# test2.net
KiCad netlist of a schematic drawn in EAGLE
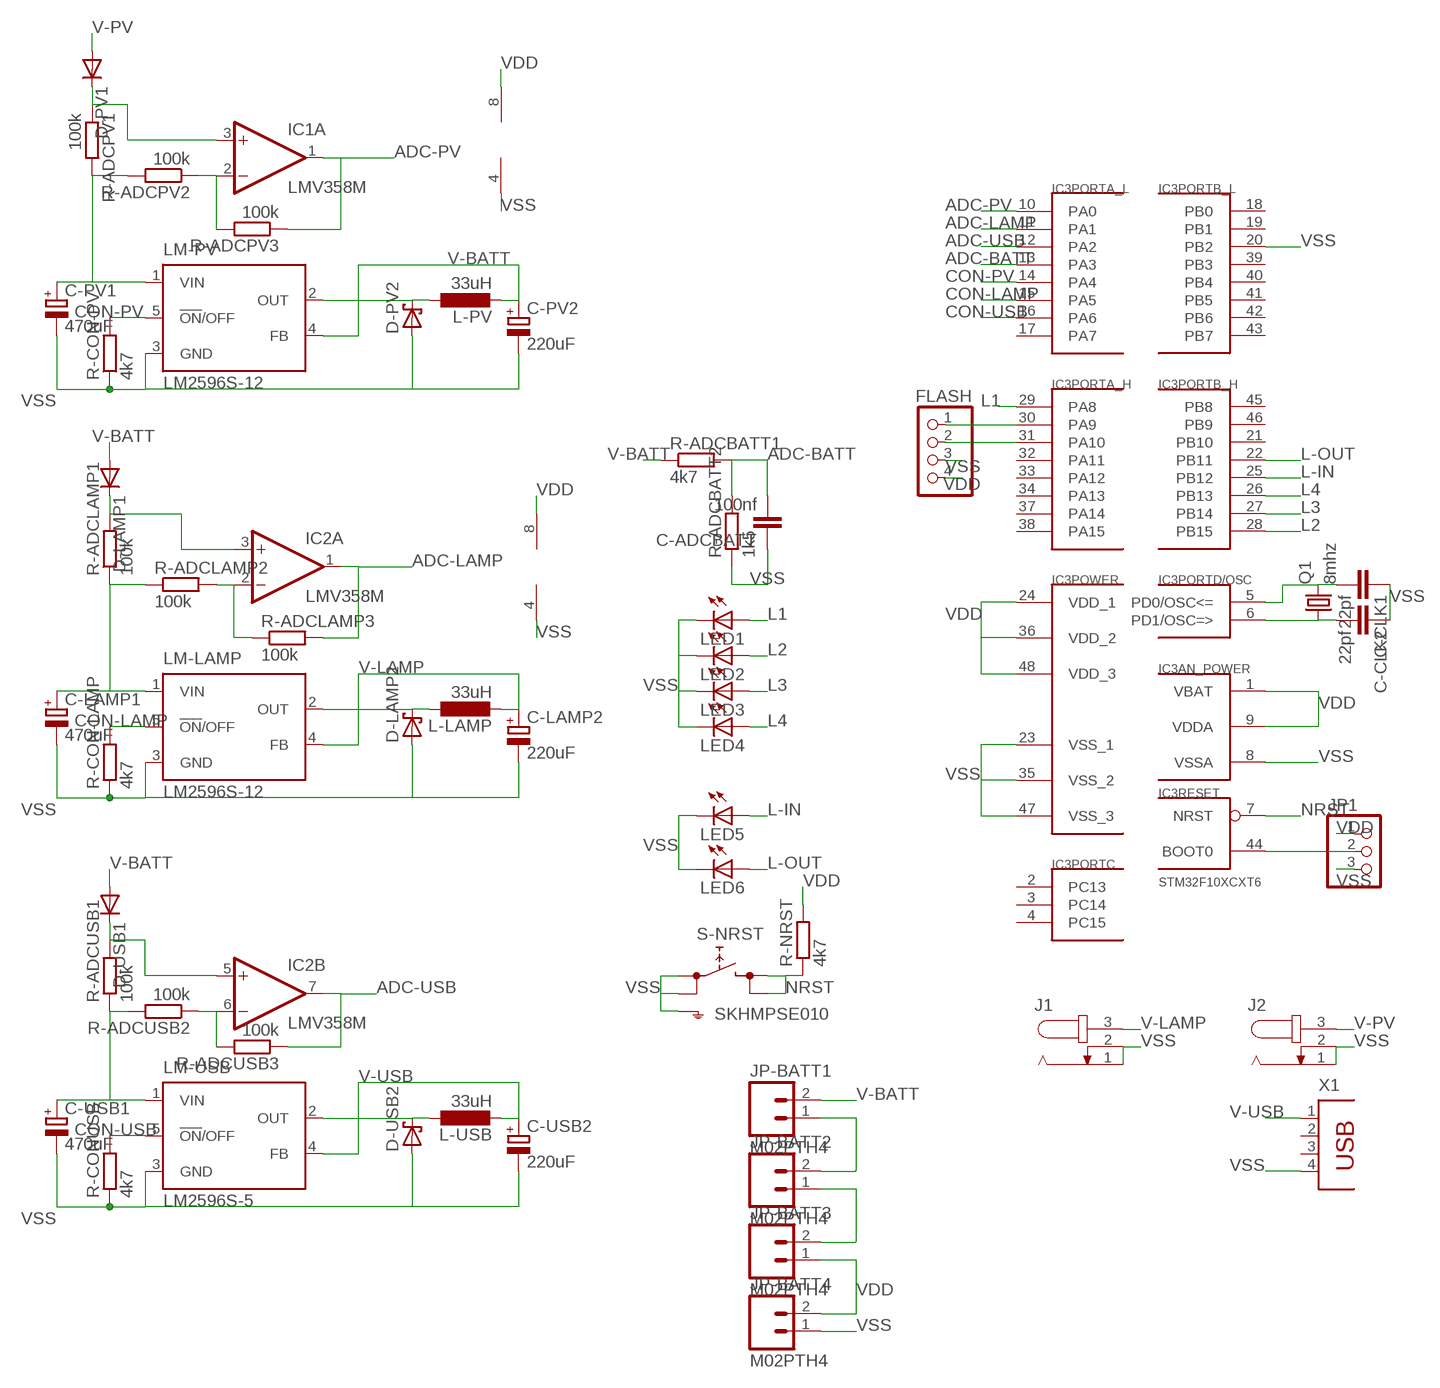
[diagram p0: schematic, sheet 1]

(export (version "E")
  (design (tool "Eeschema 10.0.6"))
  (components
    (comp (ref "C-ADCBATT")
      (value "100nf")
      (footprint "eagle-import:C0805")
      (libsource (lib "eagle-import") (part "C-EUC0805"))
    )
    (comp (ref "C-CLK1")
      (value "22pf")
      (footprint "eagle-import:C0805")
      (libsource (lib "eagle-import") (part "C-EUC0805"))
    )
    (comp (ref "C-CLK2")
      (value "22pf")
      (footprint "eagle-import:C0805")
      (libsource (lib "eagle-import") (part "C-EUC0805"))
    )
    (comp (ref "C-LAMP1")
      (value "470uF")
      (footprint "eagle-import:E2,5-5")
      (libsource (lib "eagle-import") (part "CPOL-EUE2.5-5"))
    )
    (comp (ref "C-LAMP2")
      (value "220uF")
      (footprint "eagle-import:E2,5-5")
      (libsource (lib "eagle-import") (part "CPOL-EUE2.5-5"))
    )
    (comp (ref "C-PV1")
      (value "470uF")
      (footprint "eagle-import:E2,5-5")
      (libsource (lib "eagle-import") (part "CPOL-EUE2.5-5"))
    )
    (comp (ref "C-PV2")
      (value "220uF")
      (footprint "eagle-import:E2,5-5")
      (libsource (lib "eagle-import") (part "CPOL-EUE2.5-5"))
    )
    (comp (ref "C-USB1")
      (value "470uF")
      (footprint "eagle-import:E2,5-5")
      (libsource (lib "eagle-import") (part "CPOL-EUE2.5-5"))
    )
    (comp (ref "C-USB2")
      (value "220uF")
      (footprint "eagle-import:E2,5-5")
      (libsource (lib "eagle-import") (part "CPOL-EUE2.5-5"))
    )
    (comp (ref "D-LAMP1")
      (value "DIODE-DO-214AC")
      (footprint "eagle-import:DO-214AC")
      (libsource (lib "eagle-import") (part "DIODE-DO-214AC"))
    )
    (comp (ref "D-LAMP2")
      (value "SCHOTTKY-DIODE")
      (footprint "eagle-import:DIODE_SMB")
      (libsource (lib "eagle-import") (part "SCHOTTKY-DIODE"))
    )
    (comp (ref "D-PV1")
      (value "DIODE-DO-214AC")
      (footprint "eagle-import:DO-214AC")
      (libsource (lib "eagle-import") (part "DIODE-DO-214AC"))
    )
    (comp (ref "D-PV2")
      (value "SCHOTTKY-DIODE")
      (footprint "eagle-import:DIODE_SMB")
      (libsource (lib "eagle-import") (part "SCHOTTKY-DIODE"))
    )
    (comp (ref "D-USB1")
      (value "DIODE-DO-214AC")
      (footprint "eagle-import:DO-214AC")
      (libsource (lib "eagle-import") (part "DIODE-DO-214AC"))
    )
    (comp (ref "D-USB2")
      (value "SCHOTTKY-DIODE")
      (footprint "eagle-import:DIODE_SMB")
      (libsource (lib "eagle-import") (part "SCHOTTKY-DIODE"))
    )
    (comp (ref "FLASH")
      (value "PINHD-1X4")
      (footprint "eagle-import:1X04")
      (libsource (lib "eagle-import") (part "PINHD-1X4"))
    )
    (comp (ref "IC1")
      (value "LMV358M")
      (footprint "eagle-import:SO08")
      (libsource (lib "eagle-import") (part "LMV358?M"))
    )
    (comp (ref "IC2")
      (value "LMV358M")
      (footprint "eagle-import:SO08")
      (libsource (lib "eagle-import") (part "LMV358?M"))
    )
    (comp (ref "IC3")
      (value "STM32F10XCXT6")
      (footprint "eagle-import:TQFP48")
      (libsource (lib "eagle-import") (part "STM32F10XCXT6"))
    )
    (comp (ref "J1")
      (value "JACK-PLUG0")
      (footprint "eagle-import:SPC4077")
      (libsource (lib "eagle-import") (part "JACK-PLUG0"))
    )
    (comp (ref "J2")
      (value "JACK-PLUG0")
      (footprint "eagle-import:SPC4077")
      (libsource (lib "eagle-import") (part "JACK-PLUG0"))
    )
    (comp (ref "JP-BATT1")
      (value "M02PTH4")
      (footprint "eagle-import:1X02_XTRA_BIG")
      (libsource (lib "eagle-import") (part "M02PTH4"))
    )
    (comp (ref "JP-BATT2")
      (value "M02PTH4")
      (footprint "eagle-import:1X02_XTRA_BIG")
      (libsource (lib "eagle-import") (part "M02PTH4"))
    )
    (comp (ref "JP-BATT3")
      (value "M02PTH4")
      (footprint "eagle-import:1X02_XTRA_BIG")
      (libsource (lib "eagle-import") (part "M02PTH4"))
    )
    (comp (ref "JP-BATT4")
      (value "M02PTH4")
      (footprint "eagle-import:1X02_XTRA_BIG")
      (libsource (lib "eagle-import") (part "M02PTH4"))
    )
    (comp (ref "JP1")
      (value "PINHD-1X3")
      (footprint "eagle-import:1X03")
      (libsource (lib "eagle-import") (part "PINHD-1X3"))
    )
    (comp (ref "L-LAMP")
      (value "33uH")
      (footprint "eagle-import:POWER-CHOKE_WE-TPC")
      (libsource (lib "eagle-import") (part "L-EUWE-TPC"))
    )
    (comp (ref "L-PV")
      (value "33uH")
      (footprint "eagle-import:POWER-CHOKE_WE-TPC")
      (libsource (lib "eagle-import") (part "L-EUWE-TPC"))
    )
    (comp (ref "L-USB")
      (value "33uH")
      (footprint "eagle-import:POWER-CHOKE_WE-TPC")
      (libsource (lib "eagle-import") (part "L-EUWE-TPC"))
    )
    (comp (ref "LED1")
      (value "LEDCHIP-LED0805")
      (footprint "eagle-import:CHIP-LED0805")
      (libsource (lib "eagle-import") (part "LEDCHIP-LED0805"))
    )
    (comp (ref "LED2")
      (value "LEDCHIP-LED0805")
      (footprint "eagle-import:CHIP-LED0805")
      (libsource (lib "eagle-import") (part "LEDCHIP-LED0805"))
    )
    (comp (ref "LED3")
      (value "LEDCHIP-LED0805")
      (footprint "eagle-import:CHIP-LED0805")
      (libsource (lib "eagle-import") (part "LEDCHIP-LED0805"))
    )
    (comp (ref "LED4")
      (value "LEDCHIP-LED0805")
      (footprint "eagle-import:CHIP-LED0805")
      (libsource (lib "eagle-import") (part "LEDCHIP-LED0805"))
    )
    (comp (ref "LED5")
      (value "LEDCHIP-LED0805")
      (footprint "eagle-import:CHIP-LED0805")
      (libsource (lib "eagle-import") (part "LEDCHIP-LED0805"))
    )
    (comp (ref "LED6")
      (value "LEDCHIP-LED0805")
      (footprint "eagle-import:CHIP-LED0805")
      (libsource (lib "eagle-import") (part "LEDCHIP-LED0805"))
    )
    (comp (ref "LM-LAMP")
      (value "LM2596S-12")
      (footprint "eagle-import:TO263-5")
      (fields (field (name "MF") "NATIONAL SEMICONDUCTOR") (field (name "MPN") "LM2596S-ADJ/NOPB"))
      (libsource (lib "eagle-import") (part "LM2596S"))
    )
    (comp (ref "LM-PV")
      (value "LM2596S-12")
      (footprint "eagle-import:TO263-5")
      (fields (field (name "MF") "NATIONAL SEMICONDUCTOR") (field (name "MPN") "LM2596S-ADJ/NOPB"))
      (libsource (lib "eagle-import") (part "LM2596S"))
    )
    (comp (ref "LM-USB")
      (value "LM2596S-5")
      (footprint "eagle-import:TO263-5")
      (fields (field (name "MF") "NATIONAL SEMICONDUCTOR") (field (name "MPN") "LM2596S-ADJ/NOPB"))
      (libsource (lib "eagle-import") (part "LM2596S"))
    )
    (comp (ref "Q1")
      (value "8mhz")
      (footprint "eagle-import:HC49_S")
      (libsource (lib "eagle-import") (part "CRYSTALHC49S"))
    )
    (comp (ref "R-ADCBATT1")
      (value "4k7")
      (footprint "eagle-import:R0805")
      (libsource (lib "eagle-import") (part "R-EU_R0805"))
    )
    (comp (ref "R-ADCBATT2")
      (value "1k5")
      (footprint "eagle-import:R0805")
      (libsource (lib "eagle-import") (part "R-EU_R0805"))
    )
    (comp (ref "R-ADCLAMP1")
      (value "100k")
      (footprint "eagle-import:R0805")
      (libsource (lib "eagle-import") (part "R-EU_R0805"))
    )
    (comp (ref "R-ADCLAMP2")
      (value "100k")
      (footprint "eagle-import:R0805")
      (libsource (lib "eagle-import") (part "R-EU_R0805"))
    )
    (comp (ref "R-ADCLAMP3")
      (value "100k")
      (footprint "eagle-import:R0805")
      (libsource (lib "eagle-import") (part "R-EU_R0805"))
    )
    (comp (ref "R-ADCPV1")
      (value "100k")
      (footprint "eagle-import:R0805")
      (libsource (lib "eagle-import") (part "R-EU_R0805"))
    )
    (comp (ref "R-ADCPV2")
      (value "100k")
      (footprint "eagle-import:R0805")
      (libsource (lib "eagle-import") (part "R-EU_R0805"))
    )
    (comp (ref "R-ADCPV3")
      (value "100k")
      (footprint "eagle-import:R0805")
      (libsource (lib "eagle-import") (part "R-EU_R0805"))
    )
    (comp (ref "R-ADCUSB1")
      (value "100k")
      (footprint "eagle-import:R0805")
      (libsource (lib "eagle-import") (part "R-EU_R0805"))
    )
    (comp (ref "R-ADCUSB2")
      (value "100k")
      (footprint "eagle-import:R0805")
      (libsource (lib "eagle-import") (part "R-EU_R0805"))
    )
    (comp (ref "R-ADCUSB3")
      (value "100k")
      (footprint "eagle-import:R0805")
      (libsource (lib "eagle-import") (part "R-EU_R0805"))
    )
    (comp (ref "R-CON-LAMP")
      (value "4k7")
      (footprint "eagle-import:R0805")
      (libsource (lib "eagle-import") (part "R-EU_R0805"))
    )
    (comp (ref "R-CON-PV")
      (value "4k7")
      (footprint "eagle-import:R0805")
      (libsource (lib "eagle-import") (part "R-EU_R0805"))
    )
    (comp (ref "R-CONUSB")
      (value "4k7")
      (footprint "eagle-import:R0805")
      (libsource (lib "eagle-import") (part "R-EU_R0805"))
    )
    (comp (ref "R-NRST")
      (value "4k7")
      (footprint "eagle-import:R0805")
      (libsource (lib "eagle-import") (part "R-EU_R0805"))
    )
    (comp (ref "S-NRST")
      (value "SKHMPSE010")
      (footprint "eagle-import:SKHMPXE010")
      (libsource (lib "eagle-import") (part "SKHMPE010S"))
    )
    (comp (ref "X1")
      (value "PN87520")
      (footprint "eagle-import:PN87520")
      (libsource (lib "eagle-import") (part "PN87520"))
    )
  )
  (nets
    (net (code "1") (name "/ADC-BATT") (class "Default")
      (node (ref "C-ADCBATT") (pin "2") (pinfunction "2_2") (pintype "passive"))
      (node (ref "IC3") (pin "13") (pinfunction "PA3_13") (pintype "bidirectional"))
      (node (ref "R-ADCBATT1") (pin "2") (pinfunction "2_2") (pintype "passive"))
      (node (ref "R-ADCBATT2") (pin "2") (pinfunction "2_2") (pintype "passive"))
    )
    (net (code "2") (name "/ADC-LAMP") (class "Default")
      (node (ref "IC2") (pin "1") (pinfunction "OUT_1") (pintype "output"))
      (node (ref "IC3") (pin "11") (pinfunction "PA1_11") (pintype "bidirectional"))
      (node (ref "R-ADCLAMP3") (pin "2") (pinfunction "2_2") (pintype "passive"))
    )
    (net (code "3") (name "/ADC-PV") (class "Default")
      (node (ref "IC1") (pin "1") (pinfunction "OUT_1") (pintype "output"))
      (node (ref "IC3") (pin "10") (pinfunction "PA0_10") (pintype "bidirectional"))
      (node (ref "R-ADCPV3") (pin "1") (pinfunction "1_1") (pintype "passive"))
    )
    (net (code "4") (name "/ADC-USB") (class "Default")
      (node (ref "IC2") (pin "7") (pinfunction "OUT_7") (pintype "output"))
      (node (ref "IC3") (pin "12") (pinfunction "PA2_12") (pintype "bidirectional"))
      (node (ref "R-ADCUSB3") (pin "1") (pinfunction "1_1") (pintype "passive"))
    )
    (net (code "5") (name "/CON-LAMP") (class "Default")
      (node (ref "IC3") (pin "15") (pinfunction "PA5_15") (pintype "bidirectional"))
      (node (ref "LM-LAMP") (pin "5") (pinfunction "~{ON}/OFF_5") (pintype "input"))
      (node (ref "R-CON-LAMP") (pin "2") (pinfunction "2_2") (pintype "passive"))
    )
    (net (code "6") (name "/CON-PV") (class "Default")
      (node (ref "IC3") (pin "14") (pinfunction "PA4_14") (pintype "bidirectional"))
      (node (ref "LM-PV") (pin "5") (pinfunction "~{ON}/OFF_5") (pintype "input"))
      (node (ref "R-CON-PV") (pin "2") (pinfunction "2_2") (pintype "passive"))
    )
    (net (code "7") (name "/CON-USB") (class "Default")
      (node (ref "IC3") (pin "16") (pinfunction "PA6_16") (pintype "bidirectional"))
      (node (ref "LM-USB") (pin "5") (pinfunction "~{ON}/OFF_5") (pintype "input"))
      (node (ref "R-CONUSB") (pin "2") (pinfunction "2_2") (pintype "passive"))
    )
    (net (code "8") (name "/L-IN") (class "Default")
      (node (ref "IC3") (pin "25") (pinfunction "PB12_25") (pintype "bidirectional"))
      (node (ref "LED5") (pin "A") (pinfunction "A_A") (pintype "passive"))
    )
    (net (code "9") (name "/L-OUT") (class "Default")
      (node (ref "IC3") (pin "22") (pinfunction "PB11_22") (pintype "bidirectional"))
      (node (ref "LED6") (pin "A") (pinfunction "A_A") (pintype "passive"))
    )
    (net (code "10") (name "/L1") (class "Default")
      (node (ref "IC3") (pin "29") (pinfunction "PA8_29") (pintype "bidirectional"))
      (node (ref "LED1") (pin "A") (pinfunction "A_A") (pintype "passive"))
    )
    (net (code "11") (name "/L2") (class "Default")
      (node (ref "IC3") (pin "28") (pinfunction "PB15_28") (pintype "bidirectional"))
      (node (ref "LED2") (pin "A") (pinfunction "A_A") (pintype "passive"))
    )
    (net (code "12") (name "/L3") (class "Default")
      (node (ref "IC3") (pin "27") (pinfunction "PB14_27") (pintype "bidirectional"))
      (node (ref "LED3") (pin "A") (pinfunction "A_A") (pintype "passive"))
    )
    (net (code "13") (name "/L4") (class "Default")
      (node (ref "IC3") (pin "26") (pinfunction "PB13_26") (pintype "bidirectional"))
      (node (ref "LED4") (pin "A") (pinfunction "A_A") (pintype "passive"))
    )
    (net (code "14") (name "/NRST") (class "Default")
      (node (ref "IC3") (pin "7") (pinfunction "NRST_7") (pintype "input"))
      (node (ref "R-NRST") (pin "1") (pinfunction "1_1") (pintype "passive"))
      (node (ref "S-NRST") (pin "3") (pinfunction "2.1_3") (pintype "passive"))
      (node (ref "S-NRST") (pin "4") (pinfunction "2.2_4") (pintype "passive"))
    )
    (net (code "15") (name "/V-BATT") (class "Default")
      (node (ref "C-PV2") (pin "+") (pinfunction "+_+") (pintype "passive"))
      (node (ref "D-LAMP1") (pin "A") (pinfunction "A_A") (pintype "passive"))
      (node (ref "D-USB1") (pin "A") (pinfunction "A_A") (pintype "passive"))
      (node (ref "JP-BATT1") (pin "2") (pinfunction "2_2") (pintype "passive"))
      (node (ref "L-PV") (pin "2") (pinfunction "2_2") (pintype "passive"))
      (node (ref "LM-PV") (pin "4") (pinfunction "FB_4") (pintype "input"))
      (node (ref "R-ADCBATT1") (pin "1") (pinfunction "1_1") (pintype "passive"))
    )
    (net (code "16") (name "/V-LAMP") (class "Default")
      (node (ref "C-LAMP2") (pin "+") (pinfunction "+_+") (pintype "passive"))
      (node (ref "J1") (pin "3") (pinfunction "3_3") (pintype "passive"))
      (node (ref "L-LAMP") (pin "2") (pinfunction "2_2") (pintype "passive"))
      (node (ref "LM-LAMP") (pin "4") (pinfunction "FB_4") (pintype "input"))
    )
    (net (code "17") (name "/V-PV") (class "Default")
      (node (ref "D-PV1") (pin "A") (pinfunction "A_A") (pintype "passive"))
      (node (ref "J2") (pin "3") (pinfunction "3_3") (pintype "passive"))
    )
    (net (code "18") (name "/V-USB") (class "Default")
      (node (ref "C-USB2") (pin "+") (pinfunction "+_+") (pintype "passive"))
      (node (ref "L-USB") (pin "2") (pinfunction "2_2") (pintype "passive"))
      (node (ref "LM-USB") (pin "4") (pinfunction "FB_4") (pintype "input"))
      (node (ref "X1") (pin "1") (pinfunction "1_1") (pintype "passive"))
    )
    (net (code "19") (name "/VDD") (class "Default")
      (node (ref "FLASH") (pin "4") (pinfunction "4_4") (pintype "passive"))
      (node (ref "IC1") (pin "8") (pinfunction "V+_8") (pintype "power_in"))
      (node (ref "IC2") (pin "8") (pinfunction "V+_8") (pintype "power_in"))
      (node (ref "IC3") (pin "1") (pinfunction "VBAT_1") (pintype "power_in"))
      (node (ref "IC3") (pin "24") (pinfunction "VDD_1_24") (pintype "power_in"))
      (node (ref "IC3") (pin "36") (pinfunction "VDD_2_36") (pintype "power_in"))
      (node (ref "IC3") (pin "48") (pinfunction "VDD_3_48") (pintype "power_in"))
      (node (ref "IC3") (pin "9") (pinfunction "VDDA_9") (pintype "power_in"))
      (node (ref "JP-BATT3") (pin "1") (pinfunction "1_1") (pintype "passive"))
      (node (ref "JP-BATT4") (pin "2") (pinfunction "2_2") (pintype "passive"))
      (node (ref "JP1") (pin "1") (pinfunction "1_1") (pintype "passive"))
      (node (ref "R-NRST") (pin "2") (pinfunction "2_2") (pintype "passive"))
    )
    (net (code "20") (name "/VSS") (class "Default")
      (node (ref "C-ADCBATT") (pin "1") (pinfunction "1_1") (pintype "passive"))
      (node (ref "C-CLK1") (pin "1") (pinfunction "1_1") (pintype "passive"))
      (node (ref "C-CLK2") (pin "1") (pinfunction "1_1") (pintype "passive"))
      (node (ref "C-LAMP1") (pin "-") (pinfunction "-_-") (pintype "passive"))
      (node (ref "C-LAMP2") (pin "-") (pinfunction "-_-") (pintype "passive"))
      (node (ref "C-PV1") (pin "-") (pinfunction "-_-") (pintype "passive"))
      (node (ref "C-PV2") (pin "-") (pinfunction "-_-") (pintype "passive"))
      (node (ref "C-USB1") (pin "-") (pinfunction "-_-") (pintype "passive"))
      (node (ref "C-USB2") (pin "-") (pinfunction "-_-") (pintype "passive"))
      (node (ref "D-LAMP2") (pin "A") (pinfunction "C_A") (pintype "passive"))
      (node (ref "D-PV2") (pin "A") (pinfunction "C_A") (pintype "passive"))
      (node (ref "D-USB2") (pin "A") (pinfunction "C_A") (pintype "passive"))
      (node (ref "FLASH") (pin "3") (pinfunction "3_3") (pintype "passive"))
      (node (ref "IC1") (pin "4") (pinfunction "V-_4") (pintype "power_in"))
      (node (ref "IC2") (pin "4") (pinfunction "V-_4") (pintype "power_in"))
      (node (ref "IC3") (pin "20") (pinfunction "PB2_20") (pintype "bidirectional"))
      (node (ref "IC3") (pin "23") (pinfunction "VSS_1_23") (pintype "power_in"))
      (node (ref "IC3") (pin "35") (pinfunction "VSS_2_35") (pintype "power_in"))
      (node (ref "IC3") (pin "47") (pinfunction "VSS_3_47") (pintype "power_in"))
      (node (ref "IC3") (pin "8") (pinfunction "VSSA_8") (pintype "power_in"))
      (node (ref "J1") (pin "1") (pinfunction "1_1") (pintype "passive"))
      (node (ref "J1") (pin "2") (pinfunction "2_2") (pintype "passive"))
      (node (ref "J2") (pin "1") (pinfunction "1_1") (pintype "passive"))
      (node (ref "J2") (pin "2") (pinfunction "2_2") (pintype "passive"))
      (node (ref "JP-BATT4") (pin "1") (pinfunction "1_1") (pintype "passive"))
      (node (ref "JP1") (pin "3") (pinfunction "3_3") (pintype "passive"))
      (node (ref "LED1") (pin "C") (pinfunction "C_C") (pintype "passive"))
      (node (ref "LED2") (pin "C") (pinfunction "C_C") (pintype "passive"))
      (node (ref "LED3") (pin "C") (pinfunction "C_C") (pintype "passive"))
      (node (ref "LED4") (pin "C") (pinfunction "C_C") (pintype "passive"))
      (node (ref "LED5") (pin "C") (pinfunction "C_C") (pintype "passive"))
      (node (ref "LED6") (pin "C") (pinfunction "C_C") (pintype "passive"))
      (node (ref "LM-LAMP") (pin "3") (pinfunction "GND_3") (pintype "power_in"))
      (node (ref "LM-PV") (pin "3") (pinfunction "GND_3") (pintype "power_in"))
      (node (ref "LM-USB") (pin "3") (pinfunction "GND_3") (pintype "power_in"))
      (node (ref "R-ADCBATT2") (pin "1") (pinfunction "1_1") (pintype "passive"))
      (node (ref "R-CON-LAMP") (pin "1") (pinfunction "1_1") (pintype "passive"))
      (node (ref "R-CON-PV") (pin "1") (pinfunction "1_1") (pintype "passive"))
      (node (ref "R-CONUSB") (pin "1") (pinfunction "1_1") (pintype "passive"))
      (node (ref "S-NRST") (pin "1") (pinfunction "1.1_1") (pintype "passive"))
      (node (ref "S-NRST") (pin "2") (pinfunction "1.2_2") (pintype "passive"))
      (node (ref "S-NRST") (pin "5") (pinfunction "SH_5") (pintype "passive"))
      (node (ref "X1") (pin "4") (pinfunction "4_4") (pintype "passive"))
    )
    (net (code "21") (name "Net-(D-LAMP2-A)") (class "Default")
      (node (ref "D-LAMP2") (pin "C") (pinfunction "A_C") (pintype "passive"))
      (node (ref "L-LAMP") (pin "1") (pinfunction "1_1") (pintype "passive"))
      (node (ref "LM-LAMP") (pin "2") (pinfunction "OUT_2") (pintype "output"))
    )
    (net (code "22") (name "Net-(D-PV2-A)") (class "Default")
      (node (ref "D-PV2") (pin "C") (pinfunction "A_C") (pintype "passive"))
      (node (ref "L-PV") (pin "1") (pinfunction "1_1") (pintype "passive"))
      (node (ref "LM-PV") (pin "2") (pinfunction "OUT_2") (pintype "output"))
    )
    (net (code "23") (name "Net-(D-USB2-A)") (class "Default")
      (node (ref "D-USB2") (pin "C") (pinfunction "A_C") (pintype "passive"))
      (node (ref "L-USB") (pin "1") (pinfunction "1_1") (pintype "passive"))
      (node (ref "LM-USB") (pin "2") (pinfunction "OUT_2") (pintype "output"))
    )
    (net (code "24") (name "Net-(IC1A-+IN)") (class "Default")
      (node (ref "D-PV1") (pin "C") (pinfunction "C_C") (pintype "passive"))
      (node (ref "IC1") (pin "3") (pinfunction "+IN_3") (pintype "input"))
      (node (ref "R-ADCPV1") (pin "1") (pinfunction "1_1") (pintype "passive"))
    )
    (net (code "25") (name "Net-(IC1A--IN)") (class "Default")
      (node (ref "IC1") (pin "2") (pinfunction "-IN_2") (pintype "input"))
      (node (ref "R-ADCPV2") (pin "1") (pinfunction "1_1") (pintype "passive"))
      (node (ref "R-ADCPV3") (pin "2") (pinfunction "2_2") (pintype "passive"))
    )
    (net (code "26") (name "Net-(IC2A-+IN)") (class "Default")
      (node (ref "D-LAMP1") (pin "C") (pinfunction "C_C") (pintype "passive"))
      (node (ref "IC2") (pin "3") (pinfunction "+IN_3") (pintype "input"))
      (node (ref "R-ADCLAMP1") (pin "2") (pinfunction "2_2") (pintype "passive"))
    )
    (net (code "27") (name "Net-(IC2A--IN)") (class "Default")
      (node (ref "IC2") (pin "2") (pinfunction "-IN_2") (pintype "input"))
      (node (ref "R-ADCLAMP2") (pin "2") (pinfunction "2_2") (pintype "passive"))
      (node (ref "R-ADCLAMP3") (pin "1") (pinfunction "1_1") (pintype "passive"))
    )
    (net (code "28") (name "Net-(IC2B-+IN)") (class "Default")
      (node (ref "D-USB1") (pin "C") (pinfunction "C_C") (pintype "passive"))
      (node (ref "IC2") (pin "5") (pinfunction "+IN_5") (pintype "input"))
      (node (ref "R-ADCUSB1") (pin "2") (pinfunction "2_2") (pintype "passive"))
    )
    (net (code "29") (name "Net-(IC2B--IN)") (class "Default")
      (node (ref "IC2") (pin "6") (pinfunction "-IN_6") (pintype "input"))
      (node (ref "R-ADCUSB2") (pin "1") (pinfunction "1_1") (pintype "passive"))
      (node (ref "R-ADCUSB3") (pin "2") (pinfunction "2_2") (pintype "passive"))
    )
    (net (code "30") (name "Net-(IC3B-PA9)") (class "Default")
      (node (ref "FLASH") (pin "1") (pinfunction "1_1") (pintype "passive"))
      (node (ref "IC3") (pin "30") (pinfunction "PA9_30") (pintype "bidirectional"))
    )
    (net (code "31") (name "Net-(IC3B-PA10)") (class "Default")
      (node (ref "FLASH") (pin "2") (pinfunction "2_2") (pintype "passive"))
      (node (ref "IC3") (pin "31") (pinfunction "PA10_31") (pintype "bidirectional"))
    )
    (net (code "32") (name "Net-(IC3G-PD0{slash}OSC<=)") (class "Default")
      (node (ref "C-CLK1") (pin "2") (pinfunction "2_2") (pintype "passive"))
      (node (ref "IC3") (pin "5") (pinfunction "PD0/OSC<=_5") (pintype "bidirectional"))
      (node (ref "Q1") (pin "2") (pinfunction "2_2") (pintype "passive"))
    )
    (net (code "33") (name "Net-(IC3G-PD1{slash}OSC=>)") (class "Default")
      (node (ref "C-CLK2") (pin "2") (pinfunction "2_2") (pintype "passive"))
      (node (ref "IC3") (pin "6") (pinfunction "PD1/OSC=>_6") (pintype "bidirectional"))
      (node (ref "Q1") (pin "1") (pinfunction "1_1") (pintype "passive"))
    )
    (net (code "34") (name "Net-(IC3I-BOOT0)") (class "Default")
      (node (ref "IC3") (pin "44") (pinfunction "BOOT0_44") (pintype "input"))
      (node (ref "JP1") (pin "2") (pinfunction "2_2") (pintype "passive"))
    )
    (net (code "35") (name "Net-(JP-BATT1-Pad1)") (class "Default")
      (node (ref "JP-BATT1") (pin "1") (pinfunction "1_1") (pintype "passive"))
      (node (ref "JP-BATT2") (pin "2") (pinfunction "2_2") (pintype "passive"))
    )
    (net (code "36") (name "Net-(JP-BATT2-Pad1)") (class "Default")
      (node (ref "JP-BATT2") (pin "1") (pinfunction "1_1") (pintype "passive"))
      (node (ref "JP-BATT3") (pin "2") (pinfunction "2_2") (pintype "passive"))
    )
    (net (code "37") (name "Net-(LM-LAMP-VIN)") (class "Default")
      (node (ref "C-LAMP1") (pin "+") (pinfunction "+_+") (pintype "passive"))
      (node (ref "LM-LAMP") (pin "1") (pinfunction "VIN_1") (pintype "input"))
      (node (ref "R-ADCLAMP1") (pin "1") (pinfunction "1_1") (pintype "passive"))
      (node (ref "R-ADCLAMP2") (pin "1") (pinfunction "1_1") (pintype "passive"))
    )
    (net (code "38") (name "Net-(LM-PV-VIN)") (class "Default")
      (node (ref "C-PV1") (pin "+") (pinfunction "+_+") (pintype "passive"))
      (node (ref "LM-PV") (pin "1") (pinfunction "VIN_1") (pintype "input"))
      (node (ref "R-ADCPV1") (pin "2") (pinfunction "2_2") (pintype "passive"))
      (node (ref "R-ADCPV2") (pin "2") (pinfunction "2_2") (pintype "passive"))
    )
    (net (code "39") (name "Net-(LM-USB-VIN)") (class "Default")
      (node (ref "C-USB1") (pin "+") (pinfunction "+_+") (pintype "passive"))
      (node (ref "LM-USB") (pin "1") (pinfunction "VIN_1") (pintype "input"))
      (node (ref "R-ADCUSB1") (pin "1") (pinfunction "1_1") (pintype "passive"))
      (node (ref "R-ADCUSB2") (pin "2") (pinfunction "2_2") (pintype "passive"))
    )
    (net (code "40") (name "unconnected-(IC3B-PA11-Pad32)") (class "Default")
      (node (ref "IC3") (pin "32") (pinfunction "PA11_32") (pintype "bidirectional"))
    )
    (net (code "41") (name "unconnected-(IC3B-PA12-Pad33)") (class "Default")
      (node (ref "IC3") (pin "33") (pinfunction "PA12_33") (pintype "bidirectional"))
    )
    (net (code "42") (name "unconnected-(IC3B-PA13-Pad34)") (class "Default")
      (node (ref "IC3") (pin "34") (pinfunction "PA13_34") (pintype "bidirectional"))
    )
    (net (code "43") (name "unconnected-(IC3B-PA14-Pad37)") (class "Default")
      (node (ref "IC3") (pin "37") (pinfunction "PA14_37") (pintype "bidirectional"))
    )
    (net (code "44") (name "unconnected-(IC3B-PA15-Pad38)") (class "Default")
      (node (ref "IC3") (pin "38") (pinfunction "PA15_38") (pintype "bidirectional"))
    )
    (net (code "45") (name "unconnected-(IC3C-PA7-Pad17)") (class "Default")
      (node (ref "IC3") (pin "17") (pinfunction "PA7_17") (pintype "bidirectional"))
    )
    (net (code "46") (name "unconnected-(IC3D-PB8-Pad45)") (class "Default")
      (node (ref "IC3") (pin "45") (pinfunction "PB8_45") (pintype "bidirectional"))
    )
    (net (code "47") (name "unconnected-(IC3D-PB9-Pad46)") (class "Default")
      (node (ref "IC3") (pin "46") (pinfunction "PB9_46") (pintype "bidirectional"))
    )
    (net (code "48") (name "unconnected-(IC3D-PB10-Pad21)") (class "Default")
      (node (ref "IC3") (pin "21") (pinfunction "PB10_21") (pintype "bidirectional"))
    )
    (net (code "49") (name "unconnected-(IC3E-PB0-Pad18)") (class "Default")
      (node (ref "IC3") (pin "18") (pinfunction "PB0_18") (pintype "bidirectional"))
    )
    (net (code "50") (name "unconnected-(IC3E-PB1-Pad19)") (class "Default")
      (node (ref "IC3") (pin "19") (pinfunction "PB1_19") (pintype "bidirectional"))
    )
    (net (code "51") (name "unconnected-(IC3E-PB3-Pad39)") (class "Default")
      (node (ref "IC3") (pin "39") (pinfunction "PB3_39") (pintype "bidirectional"))
    )
    (net (code "52") (name "unconnected-(IC3E-PB4-Pad40)") (class "Default")
      (node (ref "IC3") (pin "40") (pinfunction "PB4_40") (pintype "bidirectional"))
    )
    (net (code "53") (name "unconnected-(IC3E-PB5-Pad41)") (class "Default")
      (node (ref "IC3") (pin "41") (pinfunction "PB5_41") (pintype "bidirectional"))
    )
    (net (code "54") (name "unconnected-(IC3E-PB6-Pad42)") (class "Default")
      (node (ref "IC3") (pin "42") (pinfunction "PB6_42") (pintype "bidirectional"))
    )
    (net (code "55") (name "unconnected-(IC3E-PB7-Pad43)") (class "Default")
      (node (ref "IC3") (pin "43") (pinfunction "PB7_43") (pintype "bidirectional"))
    )
    (net (code "56") (name "unconnected-(IC3F-PC13-Pad2)") (class "Default")
      (node (ref "IC3") (pin "2") (pinfunction "PC13_2") (pintype "bidirectional"))
    )
    (net (code "57") (name "unconnected-(IC3F-PC14-Pad3)") (class "Default")
      (node (ref "IC3") (pin "3") (pinfunction "PC14_3") (pintype "bidirectional"))
    )
    (net (code "58") (name "unconnected-(IC3F-PC15-Pad4)") (class "Default")
      (node (ref "IC3") (pin "4") (pinfunction "PC15_4") (pintype "bidirectional"))
    )
    (net (code "59") (name "unconnected-(X1-Pad2)") (class "Default")
      (node (ref "X1") (pin "2") (pinfunction "2_2") (pintype "passive"))
    )
    (net (code "60") (name "unconnected-(X1-Pad3)") (class "Default")
      (node (ref "X1") (pin "3") (pinfunction "3_3") (pintype "passive"))
    )
  )
)
